# capacimeter-v1.net
KiCad netlist of a schematic drawn in EAGLE
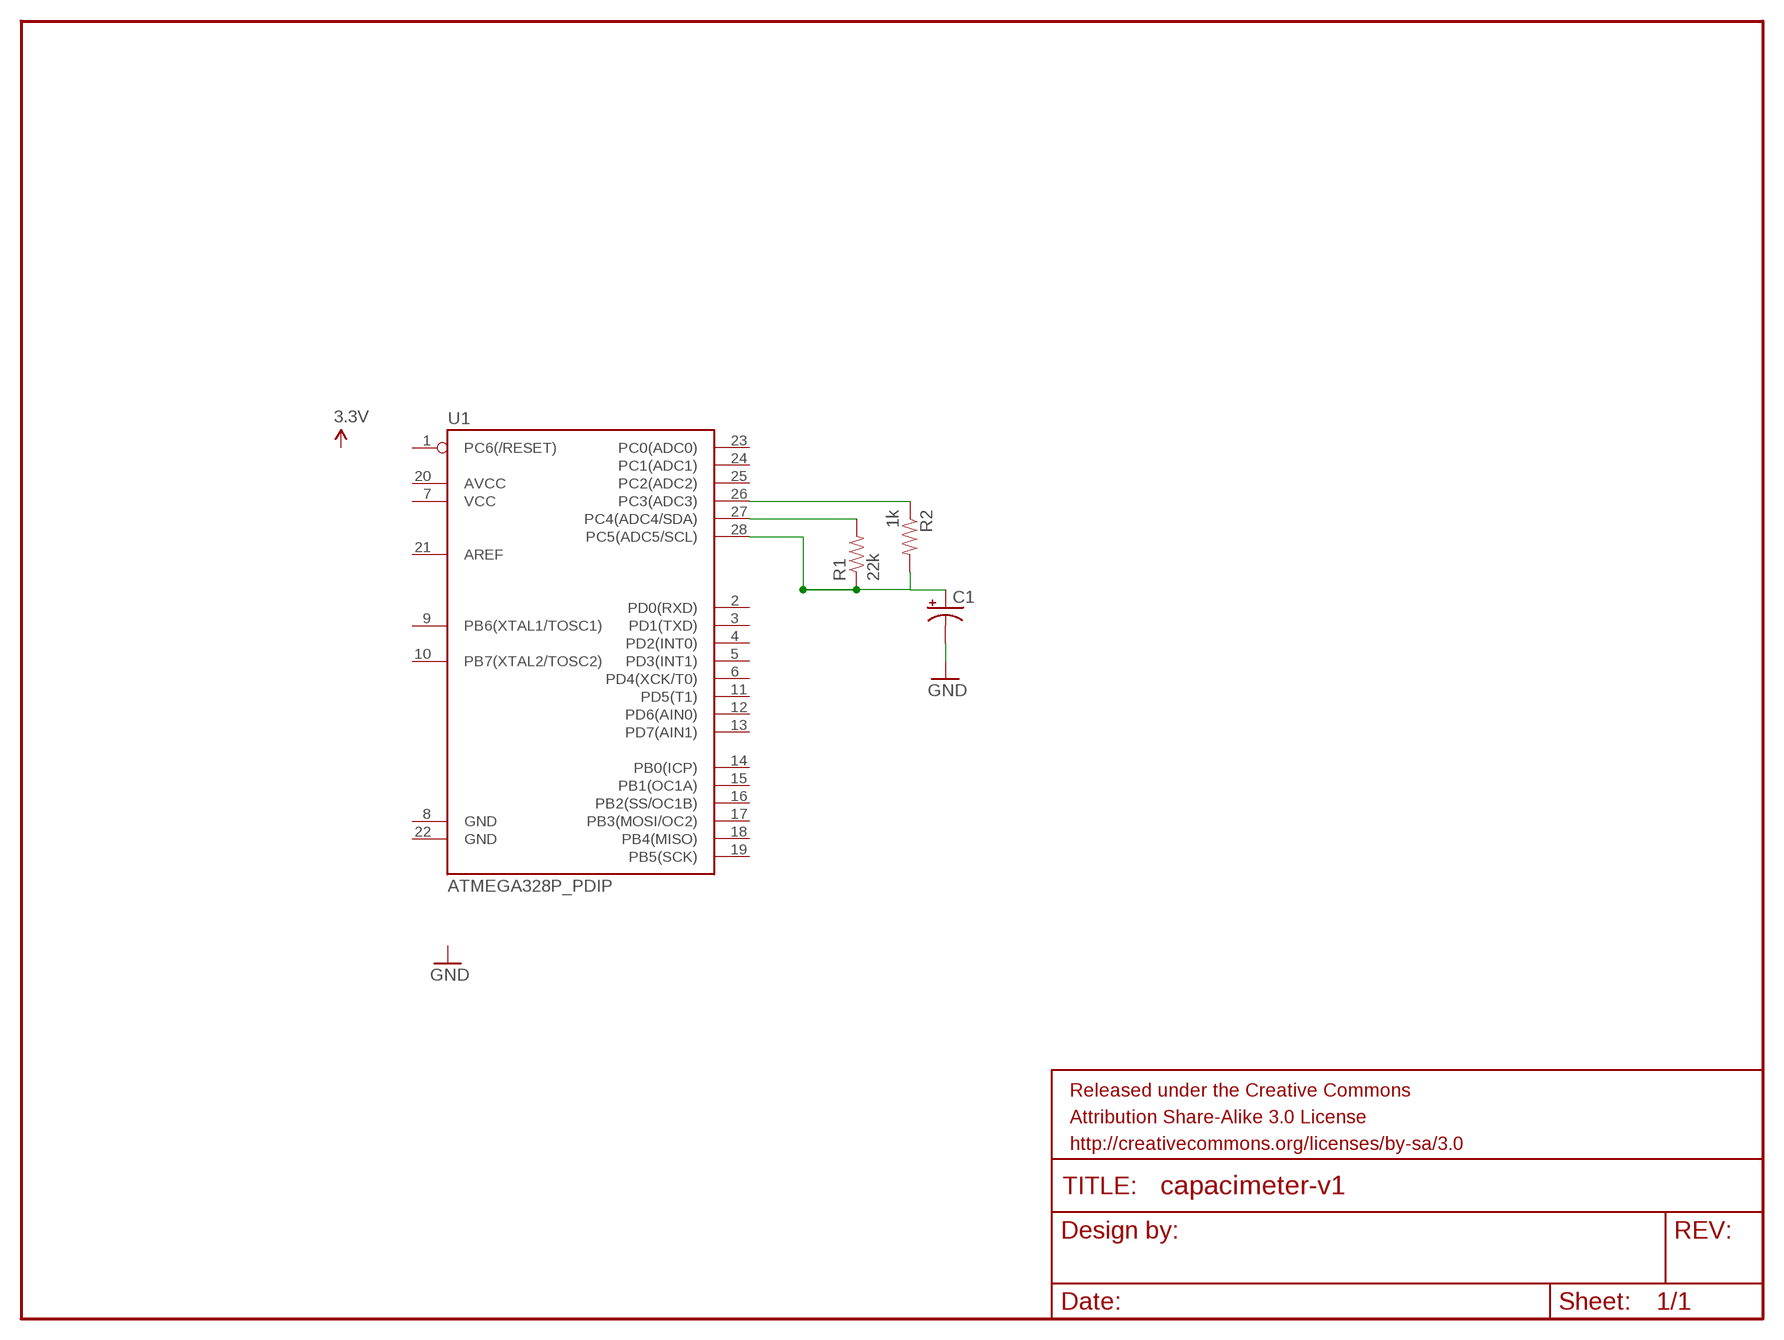
[diagram p0: schematic, sheet 1]

(export (version "E")
  (design (tool "Eeschema 10.0.6"))
  (components
    (comp (ref "C1")
      (value "CAP_POL1206")
      (footprint "eagle-import:EIA3216")
      (libsource (lib "eagle-import") (part "CAP_POL1206"))
    )
    (comp (ref "FRAME1")
      (value "FRAME-LETTER")
      (footprint "eagle-import:CREATIVE_COMMONS")
      (libsource (lib "eagle-import") (part "FRAME-LETTER"))
    )
    (comp (ref "R1")
      (value "22k")
      (footprint "eagle-import:0603-RES")
      (libsource (lib "eagle-import") (part "22M-10%"))
    )
    (comp (ref "R2")
      (value "1k")
      (footprint "eagle-import:0603-RES")
      (libsource (lib "eagle-import") (part "22M-10%"))
    )
    (comp (ref "U1")
      (value "ATMEGA328P_PDIP")
      (footprint "eagle-import:DIL28-3")
      (libsource (lib "eagle-import") (part "ATMEGA328P_PDIP"))
    )
  )
  (nets
    (net (code "2") (name "GND") (class "Default")
      (node (ref "C1") (pin "C") (pinfunction "-_C") (pintype "passive"))
    )
    (net (code "3") (name "Net-(C1-+)") (class "Default")
      (node (ref "C1") (pin "A") (pinfunction "+_A") (pintype "passive"))
      (node (ref "R1") (pin "1") (pinfunction "1_1") (pintype "passive"))
      (node (ref "R2") (pin "2") (pinfunction "2_2") (pintype "passive"))
      (node (ref "U1") (pin "28") (pinfunction "PC5(ADC5/SCL)_28") (pintype "bidirectional"))
    )
    (net (code "4") (name "Net-(U1-PC3(ADC3))") (class "Default")
      (node (ref "R2") (pin "1") (pinfunction "1_1") (pintype "passive"))
      (node (ref "U1") (pin "26") (pinfunction "PC3(ADC3)_26") (pintype "bidirectional"))
    )
    (net (code "5") (name "Net-(U1-PC4(ADC4{slash}SDA))") (class "Default")
      (node (ref "R1") (pin "2") (pinfunction "2_2") (pintype "passive"))
      (node (ref "U1") (pin "27") (pinfunction "PC4(ADC4/SDA)_27") (pintype "bidirectional"))
    )
    (net (code "6") (name "unconnected-(U1-AREF-Pad21)") (class "Default")
      (node (ref "U1") (pin "21") (pinfunction "AREF_21") (pintype "bidirectional"))
    )
    (net (code "7") (name "unconnected-(U1-AVCC-Pad20)") (class "Default")
      (node (ref "U1") (pin "20") (pinfunction "AVCC_20") (pintype "bidirectional"))
    )
    (net (code "8") (name "unconnected-(U1-GND-Pad8)") (class "Default")
      (node (ref "U1") (pin "8") (pinfunction "GND_8") (pintype "bidirectional"))
    )
    (net (code "9") (name "unconnected-(U1-GND-Pad22)") (class "Default")
      (node (ref "U1") (pin "22") (pinfunction "GND_22") (pintype "bidirectional"))
    )
    (net (code "10") (name "unconnected-(U1-PB0(ICP)-Pad14)") (class "Default")
      (node (ref "U1") (pin "14") (pinfunction "PB0(ICP)_14") (pintype "bidirectional"))
    )
    (net (code "11") (name "unconnected-(U1-PB1(OC1A)-Pad15)") (class "Default")
      (node (ref "U1") (pin "15") (pinfunction "PB1(OC1A)_15") (pintype "bidirectional"))
    )
    (net (code "12") (name "unconnected-(U1-PB2(SS{slash}OC1B)-Pad16)") (class "Default")
      (node (ref "U1") (pin "16") (pinfunction "PB2(SS/OC1B)_16") (pintype "bidirectional"))
    )
    (net (code "13") (name "unconnected-(U1-PB3(MOSI{slash}OC2)-Pad17)") (class "Default")
      (node (ref "U1") (pin "17") (pinfunction "PB3(MOSI/OC2)_17") (pintype "bidirectional"))
    )
    (net (code "14") (name "unconnected-(U1-PB4(MISO)-Pad18)") (class "Default")
      (node (ref "U1") (pin "18") (pinfunction "PB4(MISO)_18") (pintype "bidirectional"))
    )
    (net (code "15") (name "unconnected-(U1-PB5(SCK)-Pad19)") (class "Default")
      (node (ref "U1") (pin "19") (pinfunction "PB5(SCK)_19") (pintype "bidirectional"))
    )
    (net (code "16") (name "unconnected-(U1-PB6(XTAL1{slash}TOSC1)-Pad9)") (class "Default")
      (node (ref "U1") (pin "9") (pinfunction "PB6(XTAL1/TOSC1)_9") (pintype "bidirectional"))
    )
    (net (code "17") (name "unconnected-(U1-PB7(XTAL2{slash}TOSC2)-Pad10)") (class "Default")
      (node (ref "U1") (pin "10") (pinfunction "PB7(XTAL2/TOSC2)_10") (pintype "bidirectional"))
    )
    (net (code "18") (name "unconnected-(U1-PC0(ADC0)-Pad23)") (class "Default")
      (node (ref "U1") (pin "23") (pinfunction "PC0(ADC0)_23") (pintype "bidirectional"))
    )
    (net (code "19") (name "unconnected-(U1-PC1(ADC1)-Pad24)") (class "Default")
      (node (ref "U1") (pin "24") (pinfunction "PC1(ADC1)_24") (pintype "bidirectional"))
    )
    (net (code "20") (name "unconnected-(U1-PC2(ADC2)-Pad25)") (class "Default")
      (node (ref "U1") (pin "25") (pinfunction "PC2(ADC2)_25") (pintype "bidirectional"))
    )
    (net (code "21") (name "unconnected-(U1-PC6({slash}RESET)-Pad1)") (class "Default")
      (node (ref "U1") (pin "1") (pinfunction "PC6(/RESET)_1") (pintype "bidirectional"))
    )
    (net (code "22") (name "unconnected-(U1-PD0(RXD)-Pad2)") (class "Default")
      (node (ref "U1") (pin "2") (pinfunction "PD0(RXD)_2") (pintype "bidirectional"))
    )
    (net (code "23") (name "unconnected-(U1-PD1(TXD)-Pad3)") (class "Default")
      (node (ref "U1") (pin "3") (pinfunction "PD1(TXD)_3") (pintype "bidirectional"))
    )
    (net (code "24") (name "unconnected-(U1-PD2(INT0)-Pad4)") (class "Default")
      (node (ref "U1") (pin "4") (pinfunction "PD2(INT0)_4") (pintype "bidirectional"))
    )
    (net (code "25") (name "unconnected-(U1-PD3(INT1)-Pad5)") (class "Default")
      (node (ref "U1") (pin "5") (pinfunction "PD3(INT1)_5") (pintype "bidirectional"))
    )
    (net (code "26") (name "unconnected-(U1-PD4(XCK{slash}T0)-Pad6)") (class "Default")
      (node (ref "U1") (pin "6") (pinfunction "PD4(XCK/T0)_6") (pintype "bidirectional"))
    )
    (net (code "27") (name "unconnected-(U1-PD5(T1)-Pad11)") (class "Default")
      (node (ref "U1") (pin "11") (pinfunction "PD5(T1)_11") (pintype "bidirectional"))
    )
    (net (code "28") (name "unconnected-(U1-PD6(AIN0)-Pad12)") (class "Default")
      (node (ref "U1") (pin "12") (pinfunction "PD6(AIN0)_12") (pintype "bidirectional"))
    )
    (net (code "29") (name "unconnected-(U1-PD7(AIN1)-Pad13)") (class "Default")
      (node (ref "U1") (pin "13") (pinfunction "PD7(AIN1)_13") (pintype "bidirectional"))
    )
    (net (code "30") (name "unconnected-(U1-VCC-Pad7)") (class "Default")
      (node (ref "U1") (pin "7") (pinfunction "VCC_7") (pintype "bidirectional"))
    )
  )
)
